# sensor_boom.net
KiCad netlist of a schematic drawn in Altium Designer
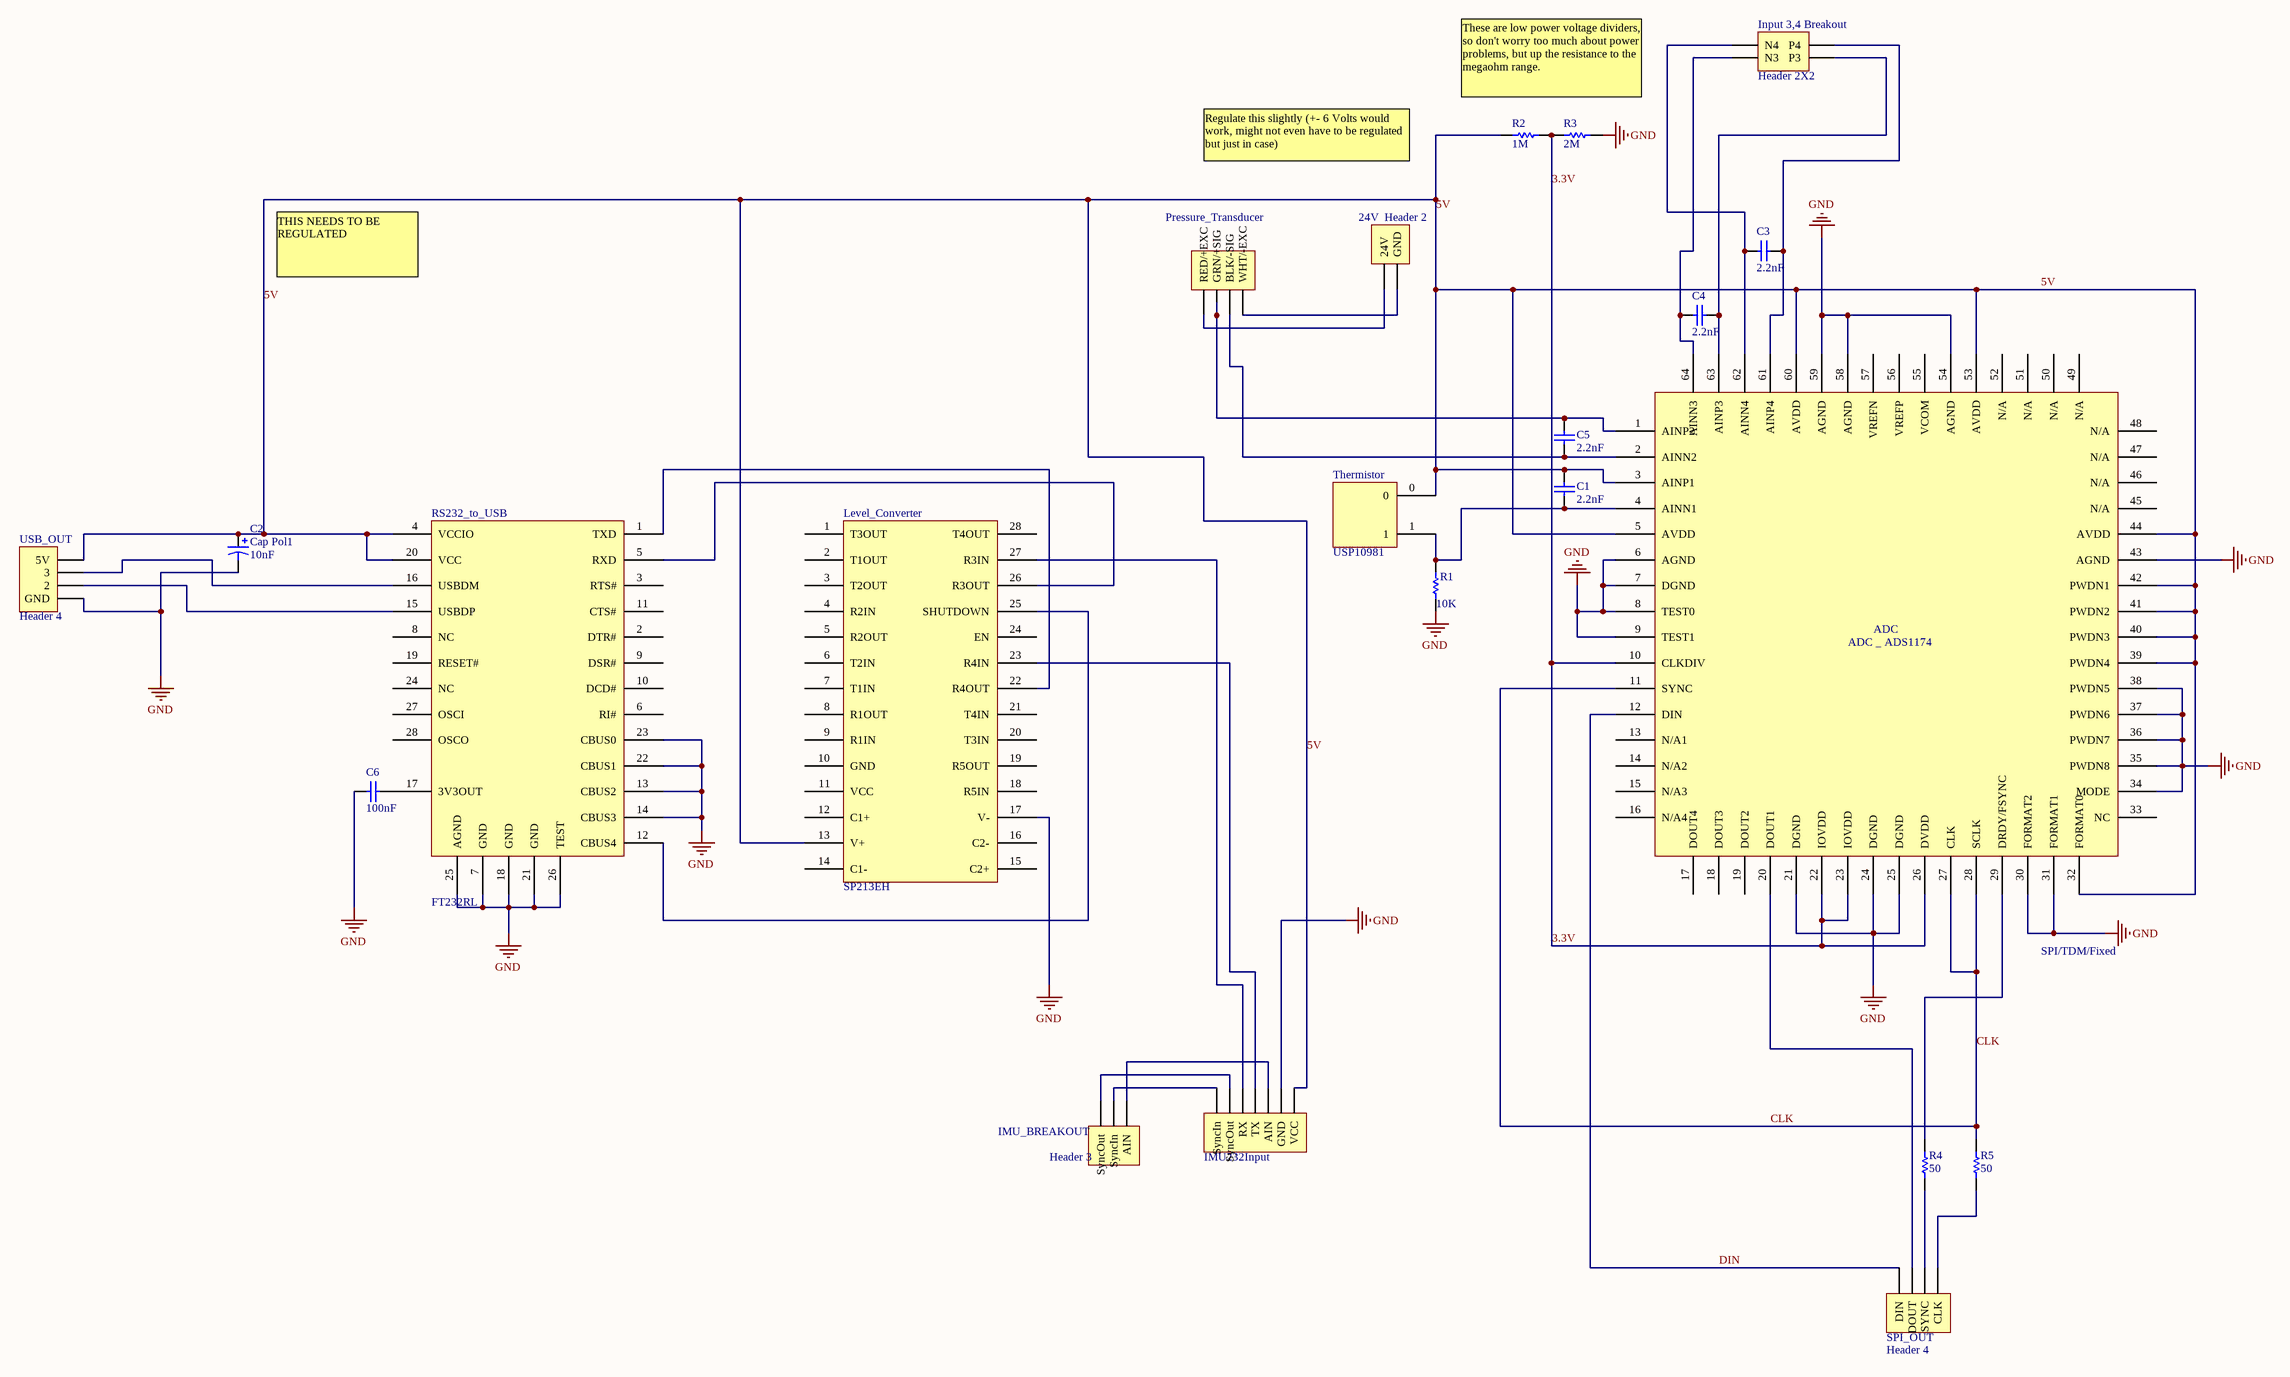
[diagram p0: sensor_boom.SchDoc]

(export (version "E")
  (design (tool "Eeschema 10.0.6"))
  (components
    (comp (ref "24V")
      (value "Header 2")
      (footprint "HDR1X2")
      (description "Header, 2-Pin")
      (fields (field (name "PUBLISHER") "Altium Limited"))
      (libsource (lib "Miscellaneous Connectors") (part "Header 2"))
    )
    (comp (ref "ADC")
      (value "ADC _ ADS1174")
      (footprint "ADC - ADS1174")
      (libsource (lib "sensor_boom") (part "ADC _ ADS1174"))
    )
    (comp (ref "C1")
      (value "2.2nF")
      (footprint "RAD-0.3")
      (description "Capacitor")
      (fields (field (name "Comment") "Cap") (field (name "PUBLISHER") "Altium Limited"))
      (libsource (lib "Miscellaneous Devices") (part "Cap"))
    )
    (comp (ref "C2")
      (value "Cap Pol1")
      (footprint "RB7.6-15")
      (description "Polarized Capacitor (Radial)")
      (fields (field (name "ALTIUM_VALUE") "10nF") (field (name "PUBLISHER") "Altium Limited"))
      (libsource (lib "Miscellaneous Devices") (part "Cap Pol1"))
    )
    (comp (ref "C3")
      (value "2.2nF")
      (footprint "RAD-0.3")
      (description "Capacitor")
      (fields (field (name "Comment") "Cap") (field (name "PUBLISHER") "Altium Limited"))
      (libsource (lib "Miscellaneous Devices") (part "Cap"))
    )
    (comp (ref "C4")
      (value "2.2nF")
      (footprint "RAD-0.3")
      (description "Capacitor")
      (fields (field (name "Comment") "Cap") (field (name "PUBLISHER") "Altium Limited"))
      (libsource (lib "Miscellaneous Devices") (part "Cap"))
    )
    (comp (ref "C5")
      (value "2.2nF")
      (footprint "RAD-0.3")
      (description "Capacitor")
      (fields (field (name "Comment") "Cap") (field (name "PUBLISHER") "Altium Limited"))
      (libsource (lib "Miscellaneous Devices") (part "Cap"))
    )
    (comp (ref "C6")
      (value "100nF")
      (footprint "RAD-0.3")
      (description "Capacitor")
      (fields (field (name "Comment") "Cap") (field (name "PUBLISHER") "Altium Limited"))
      (libsource (lib "Miscellaneous Devices") (part "Cap"))
    )
    (comp (ref "IMU232Input")
      (value "Header 7")
      (footprint "HDR1X7")
      (description "Header, 7-Pin")
      (fields (field (name "PUBLISHER") "Altium Limited"))
      (libsource (lib "Miscellaneous Connectors") (part "Header 7"))
    )
    (comp (ref "IMU_BREAKOUT")
      (value "Header 3")
      (footprint "HDR1X3")
      (description "Header, 3-Pin")
      (fields (field (name "PUBLISHER") "Altium Limited"))
      (libsource (lib "Miscellaneous Connectors") (part "Header 3"))
    )
    (comp (ref "Input 3,4 Breakout")
      (value "Header 2X2")
      (footprint "HDR2X2")
      (description "Header, 2-Pin, Dual row")
      (fields (field (name "PUBLISHER") "Altium Limited"))
      (libsource (lib "Miscellaneous Connectors") (part "Header 2X2"))
    )
    (comp (ref "Level_Converter")
      (value "SP213EH")
      (footprint "SSOP-28(2)")
      (libsource (lib "sensor_boom") (part "SP213EH"))
    )
    (comp (ref "Pressure_Transducer")
      (value "Header 4")
      (footprint "HDR1X4")
      (description "Header, 4-Pin")
      (fields (field (name "PUBLISHER") "Altium Limited"))
      (libsource (lib "") (part "Header 4_1"))
    )
    (comp (ref "R1")
      (value "10K")
      (footprint "AXIAL-0.3")
      (description "Resistor")
      (fields (field (name "Comment") "Res1") (field (name "PUBLISHER") "Altium Limited"))
      (libsource (lib "Miscellaneous Devices") (part "Res1"))
    )
    (comp (ref "R2")
      (value "1M")
      (footprint "AXIAL-0.3")
      (description "Resistor")
      (fields (field (name "Comment") "Res1") (field (name "PUBLISHER") "Altium Limited"))
      (libsource (lib "Miscellaneous Devices") (part "Res1"))
    )
    (comp (ref "R3")
      (value "2M")
      (footprint "AXIAL-0.3")
      (description "Resistor")
      (fields (field (name "Comment") "Res1") (field (name "PUBLISHER") "Altium Limited"))
      (libsource (lib "Miscellaneous Devices") (part "Res1"))
    )
    (comp (ref "R4")
      (value "50")
      (footprint "AXIAL-0.3")
      (description "Resistor")
      (fields (field (name "Comment") "Res1") (field (name "PUBLISHER") "Altium Limited"))
      (libsource (lib "Miscellaneous Devices") (part "Res1"))
    )
    (comp (ref "R5")
      (value "50")
      (footprint "AXIAL-0.3")
      (description "Resistor")
      (fields (field (name "Comment") "Res1") (field (name "PUBLISHER") "Altium Limited"))
      (libsource (lib "Miscellaneous Devices") (part "Res1"))
    )
    (comp (ref "RS232_to_USB")
      (value "FT232RL")
      (footprint "SSOP-28")
      (libsource (lib "sensor_boom") (part "FT232RL"))
    )
    (comp (ref "SPI_OUT")
      (value "Header 4")
      (footprint "HDR1X4")
      (description "Header, 4-Pin")
      (fields (field (name "PUBLISHER") "Altium Limited"))
      (libsource (lib "") (part "Header 4_2"))
    )
    (comp (ref "Thermistor")
      (value "USP10981")
      (footprint "Thermistor")
      (libsource (lib "sensor_boom") (part "USP10981"))
    )
    (comp (ref "USB_OUT")
      (value "Header 4")
      (footprint "HDR1X4")
      (description "Header, 4-Pin")
      (fields (field (name "PUBLISHER") "Altium Limited"))
      (libsource (lib "Miscellaneous Connectors") (part "Header 4"))
    )
  )
  (nets
    (net (code "1") (name "/3.3V") (class "Default")
      (node (ref "ADC") (pin "10") (pinfunction "CLKDIV_10") (pintype "passive"))
      (node (ref "ADC") (pin "22") (pinfunction "IOVDD_22") (pintype "passive"))
      (node (ref "ADC") (pin "23") (pinfunction "IOVDD_23") (pintype "passive"))
      (node (ref "ADC") (pin "26") (pinfunction "DVDD_26") (pintype "passive"))
      (node (ref "R2") (pin "2") (pinfunction "2_2") (pintype "passive"))
      (node (ref "R3") (pin "1") (pinfunction "1_1") (pintype "passive"))
    )
    (net (code "2") (name "/5V") (class "Default")
      (node (ref "ADC") (pin "3") (pinfunction "AINP1_3") (pintype "passive"))
      (node (ref "ADC") (pin "32") (pinfunction "FORMAT0_32") (pintype "passive"))
      (node (ref "ADC") (pin "39") (pinfunction "PWDN4_39") (pintype "passive"))
      (node (ref "ADC") (pin "40") (pinfunction "PWDN3_40") (pintype "passive"))
      (node (ref "ADC") (pin "41") (pinfunction "PWDN2_41") (pintype "passive"))
      (node (ref "ADC") (pin "42") (pinfunction "PWDN1_42") (pintype "passive"))
      (node (ref "ADC") (pin "44") (pinfunction "AVDD_44") (pintype "passive"))
      (node (ref "ADC") (pin "5") (pinfunction "AVDD_5") (pintype "passive"))
      (node (ref "ADC") (pin "53") (pinfunction "AVDD_53") (pintype "passive"))
      (node (ref "ADC") (pin "60") (pinfunction "AVDD_60") (pintype "passive"))
      (node (ref "C1") (pin "2") (pinfunction "2_2") (pintype "passive"))
      (node (ref "C2") (pin "1") (pinfunction "1_1") (pintype "passive"))
      (node (ref "IMU232Input") (pin "7") (pinfunction "VCC_7") (pintype "passive"))
      (node (ref "Level_Converter") (pin "13") (pinfunction "V+_13") (pintype "passive"))
      (node (ref "R2") (pin "1") (pinfunction "1_1") (pintype "passive"))
      (node (ref "RS232_to_USB") (pin "20") (pinfunction "VCC_20") (pintype "passive"))
      (node (ref "RS232_to_USB") (pin "4") (pinfunction "VCCIO_4") (pintype "passive"))
      (node (ref "Thermistor") (pin "0") (pinfunction "0_0") (pintype "passive"))
      (node (ref "USB_OUT") (pin "4") (pinfunction "5V_4") (pintype "passive"))
    )
    (net (code "3") (name "/CLK") (class "Default")
      (node (ref "ADC") (pin "11") (pinfunction "SYNC_11") (pintype "passive"))
      (node (ref "ADC") (pin "27") (pinfunction "CLK_27") (pintype "passive"))
      (node (ref "ADC") (pin "28") (pinfunction "SCLK_28") (pintype "passive"))
      (node (ref "R5") (pin "2") (pinfunction "2_2") (pintype "passive"))
    )
    (net (code "4") (name "/DIN") (class "Default")
      (node (ref "ADC") (pin "12") (pinfunction "DIN_12") (pintype "passive"))
      (node (ref "SPI_OUT") (pin "4") (pinfunction "DIN_4") (pintype "passive"))
    )
    (net (code "5") (name "GND") (class "Default")
      (node (ref "ADC") (pin "21") (pinfunction "DGND_21") (pintype "passive"))
      (node (ref "ADC") (pin "24") (pinfunction "DGND_24") (pintype "passive"))
      (node (ref "ADC") (pin "25") (pinfunction "DGND_25") (pintype "passive"))
      (node (ref "ADC") (pin "30") (pinfunction "FORMAT2_30") (pintype "passive"))
      (node (ref "ADC") (pin "31") (pinfunction "FORMAT1_31") (pintype "passive"))
      (node (ref "ADC") (pin "34") (pinfunction "MODE_34") (pintype "passive"))
      (node (ref "ADC") (pin "35") (pinfunction "PWDN8_35") (pintype "passive"))
      (node (ref "ADC") (pin "36") (pinfunction "PWDN7_36") (pintype "passive"))
      (node (ref "ADC") (pin "37") (pinfunction "PWDN6_37") (pintype "passive"))
      (node (ref "ADC") (pin "38") (pinfunction "PWDN5_38") (pintype "passive"))
      (node (ref "ADC") (pin "43") (pinfunction "AGND_43") (pintype "passive"))
      (node (ref "ADC") (pin "54") (pinfunction "AGND_54") (pintype "passive"))
      (node (ref "ADC") (pin "58") (pinfunction "AGND_58") (pintype "passive"))
      (node (ref "ADC") (pin "59") (pinfunction "AGND_59") (pintype "passive"))
      (node (ref "ADC") (pin "6") (pinfunction "AGND_6") (pintype "passive"))
      (node (ref "ADC") (pin "7") (pinfunction "DGND_7") (pintype "passive"))
      (node (ref "ADC") (pin "8") (pinfunction "TEST0_8") (pintype "passive"))
      (node (ref "ADC") (pin "9") (pinfunction "TEST1_9") (pintype "passive"))
      (node (ref "C2") (pin "2") (pinfunction "2_2") (pintype "passive"))
      (node (ref "C6") (pin "1") (pinfunction "1_1") (pintype "passive"))
      (node (ref "IMU232Input") (pin "6") (pinfunction "GND_6") (pintype "passive"))
      (node (ref "Level_Converter") (pin "17") (pinfunction "V-_17") (pintype "passive"))
      (node (ref "R1") (pin "1") (pinfunction "1_1") (pintype "passive"))
      (node (ref "R3") (pin "2") (pinfunction "2_2") (pintype "passive"))
      (node (ref "RS232_to_USB") (pin "13") (pinfunction "CBUS2_13") (pintype "passive"))
      (node (ref "RS232_to_USB") (pin "14") (pinfunction "CBUS3_14") (pintype "passive"))
      (node (ref "RS232_to_USB") (pin "18") (pinfunction "GND_18") (pintype "passive"))
      (node (ref "RS232_to_USB") (pin "21") (pinfunction "GND_21") (pintype "passive"))
      (node (ref "RS232_to_USB") (pin "22") (pinfunction "CBUS1_22") (pintype "passive"))
      (node (ref "RS232_to_USB") (pin "23") (pinfunction "CBUS0_23") (pintype "passive"))
      (node (ref "RS232_to_USB") (pin "25") (pinfunction "AGND_25") (pintype "passive"))
      (node (ref "RS232_to_USB") (pin "26") (pinfunction "TEST_26") (pintype "passive"))
      (node (ref "RS232_to_USB") (pin "7") (pinfunction "GND_7") (pintype "passive"))
      (node (ref "USB_OUT") (pin "1") (pinfunction "GND_1") (pintype "passive"))
    )
    (net (code "6") (name "Net-(24V-24V)") (class "Default")
      (node (ref "24V") (pin "1") (pinfunction "24V_1") (pintype "passive"))
      (node (ref "Pressure_Transducer") (pin "1") (pinfunction "RED/+EXC_1") (pintype "passive"))
    )
    (net (code "7") (name "Net-(24V-GND)") (class "Default")
      (node (ref "24V") (pin "2") (pinfunction "GND_2") (pintype "passive"))
      (node (ref "Pressure_Transducer") (pin "4") (pinfunction "WHT/-EXC_4") (pintype "passive"))
    )
    (net (code "8") (name "Net-(ADC-AINN1)") (class "Default")
      (node (ref "ADC") (pin "4") (pinfunction "AINN1_4") (pintype "passive"))
      (node (ref "C1") (pin "1") (pinfunction "1_1") (pintype "passive"))
      (node (ref "R1") (pin "2") (pinfunction "2_2") (pintype "passive"))
      (node (ref "Thermistor") (pin "1") (pinfunction "1_1") (pintype "passive"))
    )
    (net (code "9") (name "Net-(ADC-AINN2)") (class "Default")
      (node (ref "ADC") (pin "2") (pinfunction "AINN2_2") (pintype "passive"))
      (node (ref "C5") (pin "1") (pinfunction "1_1") (pintype "passive"))
      (node (ref "Pressure_Transducer") (pin "3") (pinfunction "BLK/-SIG_3") (pintype "passive"))
    )
    (net (code "10") (name "Net-(ADC-AINN3)") (class "Default")
      (node (ref "ADC") (pin "64") (pinfunction "AINN3_64") (pintype "passive"))
      (node (ref "C4") (pin "2") (pinfunction "2_2") (pintype "passive"))
      (node (ref "Input 3,4 Breakout") (pin "2") (pinfunction "N3_2") (pintype "passive"))
    )
    (net (code "11") (name "Net-(ADC-AINN4)") (class "Default")
      (node (ref "ADC") (pin "62") (pinfunction "AINN4_62") (pintype "passive"))
      (node (ref "C3") (pin "2") (pinfunction "2_2") (pintype "passive"))
      (node (ref "Input 3,4 Breakout") (pin "4") (pinfunction "N4_4") (pintype "passive"))
    )
    (net (code "12") (name "Net-(ADC-AINP2)") (class "Default")
      (node (ref "ADC") (pin "1") (pinfunction "AINP2_1") (pintype "passive"))
      (node (ref "C5") (pin "2") (pinfunction "2_2") (pintype "passive"))
      (node (ref "Pressure_Transducer") (pin "2") (pinfunction "GRN/+SIG_2") (pintype "passive"))
    )
    (net (code "13") (name "Net-(ADC-AINP3)") (class "Default")
      (node (ref "ADC") (pin "63") (pinfunction "AINP3_63") (pintype "passive"))
      (node (ref "C4") (pin "1") (pinfunction "1_1") (pintype "passive"))
      (node (ref "Input 3,4 Breakout") (pin "1") (pinfunction "P3_1") (pintype "passive"))
    )
    (net (code "14") (name "Net-(ADC-AINP4)") (class "Default")
      (node (ref "ADC") (pin "61") (pinfunction "AINP4_61") (pintype "passive"))
      (node (ref "C3") (pin "1") (pinfunction "1_1") (pintype "passive"))
      (node (ref "Input 3,4 Breakout") (pin "3") (pinfunction "P4_3") (pintype "passive"))
    )
    (net (code "15") (name "Net-(ADC-DOUT1)") (class "Default")
      (node (ref "ADC") (pin "20") (pinfunction "DOUT1_20") (pintype "passive"))
      (node (ref "SPI_OUT") (pin "3") (pinfunction "DOUT_3") (pintype "passive"))
    )
    (net (code "16") (name "Net-(ADC-DRDY{slash}FSYNC)") (class "Default")
      (node (ref "ADC") (pin "29") (pinfunction "DRDY/FSYNC_29") (pintype "passive"))
      (node (ref "R4") (pin "2") (pinfunction "2_2") (pintype "passive"))
    )
    (net (code "17") (name "Net-(IMU232Input-AIN)") (class "Default")
      (node (ref "IMU232Input") (pin "5") (pinfunction "AIN_5") (pintype "passive"))
      (node (ref "IMU_BREAKOUT") (pin "1") (pinfunction "AIN_1") (pintype "passive"))
    )
    (net (code "18") (name "Net-(IMU232Input-RX)") (class "Default")
      (node (ref "IMU232Input") (pin "3") (pinfunction "RX_3") (pintype "passive"))
      (node (ref "Level_Converter") (pin "27") (pinfunction "R3IN_27") (pintype "passive"))
    )
    (net (code "19") (name "Net-(IMU232Input-SyncIn)") (class "Default")
      (node (ref "IMU232Input") (pin "1") (pinfunction "SyncIn_1") (pintype "passive"))
      (node (ref "IMU_BREAKOUT") (pin "2") (pinfunction "SyncIn_2") (pintype "passive"))
    )
    (net (code "20") (name "Net-(IMU232Input-SyncOut)") (class "Default")
      (node (ref "IMU232Input") (pin "2") (pinfunction "SyncOut_2") (pintype "passive"))
      (node (ref "IMU_BREAKOUT") (pin "3") (pinfunction "SyncOut_3") (pintype "passive"))
    )
    (net (code "21") (name "Net-(IMU232Input-TX)") (class "Default")
      (node (ref "IMU232Input") (pin "4") (pinfunction "TX_4") (pintype "passive"))
      (node (ref "Level_Converter") (pin "23") (pinfunction "R4IN_23") (pintype "passive"))
    )
    (net (code "22") (name "Net-(Level_Converter-R3OUT)") (class "Default")
      (node (ref "Level_Converter") (pin "26") (pinfunction "R3OUT_26") (pintype "passive"))
      (node (ref "RS232_to_USB") (pin "5") (pinfunction "RXD_5") (pintype "passive"))
    )
    (net (code "23") (name "Net-(Level_Converter-R4OUT)") (class "Default")
      (node (ref "Level_Converter") (pin "22") (pinfunction "R4OUT_22") (pintype "passive"))
      (node (ref "RS232_to_USB") (pin "1") (pinfunction "TXD_1") (pintype "passive"))
    )
    (net (code "24") (name "Net-(Level_Converter-SHUTDOWN)") (class "Default")
      (node (ref "Level_Converter") (pin "25") (pinfunction "SHUTDOWN_25") (pintype "passive"))
      (node (ref "RS232_to_USB") (pin "12") (pinfunction "CBUS4_12") (pintype "passive"))
    )
    (net (code "25") (name "Net-(RS232_to_USB-3V3OUT)") (class "Default")
      (node (ref "C6") (pin "2") (pinfunction "2_2") (pintype "passive"))
      (node (ref "RS232_to_USB") (pin "17") (pinfunction "3V3OUT_17") (pintype "passive"))
    )
    (net (code "26") (name "Net-(RS232_to_USB-USBDM)") (class "Default")
      (node (ref "RS232_to_USB") (pin "16") (pinfunction "USBDM_16") (pintype "passive"))
      (node (ref "USB_OUT") (pin "3") (pinfunction "3_3") (pintype "passive"))
    )
    (net (code "27") (name "Net-(RS232_to_USB-USBDP)") (class "Default")
      (node (ref "RS232_to_USB") (pin "15") (pinfunction "USBDP_15") (pintype "passive"))
      (node (ref "USB_OUT") (pin "2") (pinfunction "2_2") (pintype "passive"))
    )
    (net (code "28") (name "Net-(SPI_OUT-CLK)") (class "Default")
      (node (ref "R5") (pin "1") (pinfunction "1_1") (pintype "passive"))
      (node (ref "SPI_OUT") (pin "1") (pinfunction "CLK_1") (pintype "passive"))
    )
    (net (code "29") (name "Net-(SPI_OUT-SYNC)") (class "Default")
      (node (ref "R4") (pin "1") (pinfunction "1_1") (pintype "passive"))
      (node (ref "SPI_OUT") (pin "2") (pinfunction "SYNC_2") (pintype "passive"))
    )
    (net (code "30") (name "unconnected-(ADC-DOUT2-Pad19)") (class "Default")
      (node (ref "ADC") (pin "19") (pinfunction "DOUT2_19") (pintype "passive"))
    )
    (net (code "31") (name "unconnected-(ADC-DOUT3-Pad18)") (class "Default")
      (node (ref "ADC") (pin "18") (pinfunction "DOUT3_18") (pintype "passive"))
    )
    (net (code "32") (name "unconnected-(ADC-DOUT4-Pad17)") (class "Default")
      (node (ref "ADC") (pin "17") (pinfunction "DOUT4_17") (pintype "passive"))
    )
    (net (code "33") (name "unconnected-(ADC-NC-Pad33)") (class "Default")
      (node (ref "ADC") (pin "33") (pinfunction "NC_33") (pintype "passive"))
    )
    (net (code "34") (name "unconnected-(ADC-N{slash}A-Pad45)") (class "Default")
      (node (ref "ADC") (pin "45") (pinfunction "N/A_45") (pintype "passive"))
    )
    (net (code "35") (name "unconnected-(ADC-N{slash}A-Pad46)") (class "Default")
      (node (ref "ADC") (pin "46") (pinfunction "N/A_46") (pintype "passive"))
    )
    (net (code "36") (name "unconnected-(ADC-N{slash}A-Pad47)") (class "Default")
      (node (ref "ADC") (pin "47") (pinfunction "N/A_47") (pintype "passive"))
    )
    (net (code "37") (name "unconnected-(ADC-N{slash}A-Pad48)") (class "Default")
      (node (ref "ADC") (pin "48") (pinfunction "N/A_48") (pintype "passive"))
    )
    (net (code "38") (name "unconnected-(ADC-N{slash}A-Pad49)") (class "Default")
      (node (ref "ADC") (pin "49") (pinfunction "N/A_49") (pintype "passive"))
    )
    (net (code "39") (name "unconnected-(ADC-N{slash}A-Pad50)") (class "Default")
      (node (ref "ADC") (pin "50") (pinfunction "N/A_50") (pintype "passive"))
    )
    (net (code "40") (name "unconnected-(ADC-N{slash}A-Pad51)") (class "Default")
      (node (ref "ADC") (pin "51") (pinfunction "N/A_51") (pintype "passive"))
    )
    (net (code "41") (name "unconnected-(ADC-N{slash}A-Pad52)") (class "Default")
      (node (ref "ADC") (pin "52") (pinfunction "N/A_52") (pintype "passive"))
    )
    (net (code "42") (name "unconnected-(ADC-N{slash}A1-Pad13)") (class "Default")
      (node (ref "ADC") (pin "13") (pinfunction "N/A1_13") (pintype "passive"))
    )
    (net (code "43") (name "unconnected-(ADC-N{slash}A2-Pad14)") (class "Default")
      (node (ref "ADC") (pin "14") (pinfunction "N/A2_14") (pintype "passive"))
    )
    (net (code "44") (name "unconnected-(ADC-N{slash}A3-Pad15)") (class "Default")
      (node (ref "ADC") (pin "15") (pinfunction "N/A3_15") (pintype "passive"))
    )
    (net (code "45") (name "unconnected-(ADC-N{slash}A4-Pad16)") (class "Default")
      (node (ref "ADC") (pin "16") (pinfunction "N/A4_16") (pintype "passive"))
    )
    (net (code "46") (name "unconnected-(ADC-VCOM-Pad55)") (class "Default")
      (node (ref "ADC") (pin "55") (pinfunction "VCOM_55") (pintype "passive"))
    )
    (net (code "47") (name "unconnected-(ADC-VREFN-Pad57)") (class "Default")
      (node (ref "ADC") (pin "57") (pinfunction "VREFN_57") (pintype "passive"))
    )
    (net (code "48") (name "unconnected-(ADC-VREFP-Pad56)") (class "Default")
      (node (ref "ADC") (pin "56") (pinfunction "VREFP_56") (pintype "passive"))
    )
    (net (code "49") (name "unconnected-(Level_Converter-C1+-Pad12)") (class "Default")
      (node (ref "Level_Converter") (pin "12") (pinfunction "C1+_12") (pintype "passive"))
    )
    (net (code "50") (name "unconnected-(Level_Converter-C1--Pad14)") (class "Default")
      (node (ref "Level_Converter") (pin "14") (pinfunction "C1-_14") (pintype "passive"))
    )
    (net (code "51") (name "unconnected-(Level_Converter-C2+-Pad15)") (class "Default")
      (node (ref "Level_Converter") (pin "15") (pinfunction "C2+_15") (pintype "passive"))
    )
    (net (code "52") (name "unconnected-(Level_Converter-C2--Pad16)") (class "Default")
      (node (ref "Level_Converter") (pin "16") (pinfunction "C2-_16") (pintype "passive"))
    )
    (net (code "53") (name "unconnected-(Level_Converter-EN-Pad24)") (class "Default")
      (node (ref "Level_Converter") (pin "24") (pinfunction "EN_24") (pintype "passive"))
    )
    (net (code "54") (name "unconnected-(Level_Converter-GND-Pad10)") (class "Default")
      (node (ref "Level_Converter") (pin "10") (pinfunction "GND_10") (pintype "passive"))
    )
    (net (code "55") (name "unconnected-(Level_Converter-R1IN-Pad9)") (class "Default")
      (node (ref "Level_Converter") (pin "9") (pinfunction "R1IN_9") (pintype "passive"))
    )
    (net (code "56") (name "unconnected-(Level_Converter-R1OUT-Pad8)") (class "Default")
      (node (ref "Level_Converter") (pin "8") (pinfunction "R1OUT_8") (pintype "passive"))
    )
    (net (code "57") (name "unconnected-(Level_Converter-R2IN-Pad4)") (class "Default")
      (node (ref "Level_Converter") (pin "4") (pinfunction "R2IN_4") (pintype "passive"))
    )
    (net (code "58") (name "unconnected-(Level_Converter-R2OUT-Pad5)") (class "Default")
      (node (ref "Level_Converter") (pin "5") (pinfunction "R2OUT_5") (pintype "passive"))
    )
    (net (code "59") (name "unconnected-(Level_Converter-R5IN-Pad18)") (class "Default")
      (node (ref "Level_Converter") (pin "18") (pinfunction "R5IN_18") (pintype "passive"))
    )
    (net (code "60") (name "unconnected-(Level_Converter-R5OUT-Pad19)") (class "Default")
      (node (ref "Level_Converter") (pin "19") (pinfunction "R5OUT_19") (pintype "passive"))
    )
    (net (code "61") (name "unconnected-(Level_Converter-T1IN-Pad7)") (class "Default")
      (node (ref "Level_Converter") (pin "7") (pinfunction "T1IN_7") (pintype "passive"))
    )
    (net (code "62") (name "unconnected-(Level_Converter-T1OUT-Pad2)") (class "Default")
      (node (ref "Level_Converter") (pin "2") (pinfunction "T1OUT_2") (pintype "passive"))
    )
    (net (code "63") (name "unconnected-(Level_Converter-T2IN-Pad6)") (class "Default")
      (node (ref "Level_Converter") (pin "6") (pinfunction "T2IN_6") (pintype "passive"))
    )
    (net (code "64") (name "unconnected-(Level_Converter-T2OUT-Pad3)") (class "Default")
      (node (ref "Level_Converter") (pin "3") (pinfunction "T2OUT_3") (pintype "passive"))
    )
    (net (code "65") (name "unconnected-(Level_Converter-T3IN-Pad20)") (class "Default")
      (node (ref "Level_Converter") (pin "20") (pinfunction "T3IN_20") (pintype "passive"))
    )
    (net (code "66") (name "unconnected-(Level_Converter-T3OUT-Pad1)") (class "Default")
      (node (ref "Level_Converter") (pin "1") (pinfunction "T3OUT_1") (pintype "passive"))
    )
    (net (code "67") (name "unconnected-(Level_Converter-T4IN-Pad21)") (class "Default")
      (node (ref "Level_Converter") (pin "21") (pinfunction "T4IN_21") (pintype "passive"))
    )
    (net (code "68") (name "unconnected-(Level_Converter-T4OUT-Pad28)") (class "Default")
      (node (ref "Level_Converter") (pin "28") (pinfunction "T4OUT_28") (pintype "passive"))
    )
    (net (code "69") (name "unconnected-(Level_Converter-VCC-Pad11)") (class "Default")
      (node (ref "Level_Converter") (pin "11") (pinfunction "VCC_11") (pintype "passive"))
    )
    (net (code "70") (name "unconnected-(RS232_to_USB-CTS#-Pad11)") (class "Default")
      (node (ref "RS232_to_USB") (pin "11") (pinfunction "CTS#_11") (pintype "passive"))
    )
    (net (code "71") (name "unconnected-(RS232_to_USB-DCD#-Pad10)") (class "Default")
      (node (ref "RS232_to_USB") (pin "10") (pinfunction "DCD#_10") (pintype "passive"))
    )
    (net (code "72") (name "unconnected-(RS232_to_USB-DSR#-Pad9)") (class "Default")
      (node (ref "RS232_to_USB") (pin "9") (pinfunction "DSR#_9") (pintype "passive"))
    )
    (net (code "73") (name "unconnected-(RS232_to_USB-DTR#-Pad2)") (class "Default")
      (node (ref "RS232_to_USB") (pin "2") (pinfunction "DTR#_2") (pintype "passive"))
    )
    (net (code "74") (name "unconnected-(RS232_to_USB-NC-Pad8)") (class "Default")
      (node (ref "RS232_to_USB") (pin "8") (pinfunction "NC_8") (pintype "passive"))
    )
    (net (code "75") (name "unconnected-(RS232_to_USB-NC-Pad24)") (class "Default")
      (node (ref "RS232_to_USB") (pin "24") (pinfunction "NC_24") (pintype "passive"))
    )
    (net (code "76") (name "unconnected-(RS232_to_USB-OSCI-Pad27)") (class "Default")
      (node (ref "RS232_to_USB") (pin "27") (pinfunction "OSCI_27") (pintype "passive"))
    )
    (net (code "77") (name "unconnected-(RS232_to_USB-OSCO-Pad28)") (class "Default")
      (node (ref "RS232_to_USB") (pin "28") (pinfunction "OSCO_28") (pintype "passive"))
    )
    (net (code "78") (name "unconnected-(RS232_to_USB-RESET#-Pad19)") (class "Default")
      (node (ref "RS232_to_USB") (pin "19") (pinfunction "RESET#_19") (pintype "passive"))
    )
    (net (code "79") (name "unconnected-(RS232_to_USB-RI#-Pad6)") (class "Default")
      (node (ref "RS232_to_USB") (pin "6") (pinfunction "RI#_6") (pintype "passive"))
    )
    (net (code "80") (name "unconnected-(RS232_to_USB-RTS#-Pad3)") (class "Default")
      (node (ref "RS232_to_USB") (pin "3") (pinfunction "RTS#_3") (pintype "passive"))
    )
  )
)
